# ACC_ICM20948.net
KiCad netlist of a schematic drawn in Altium Designer
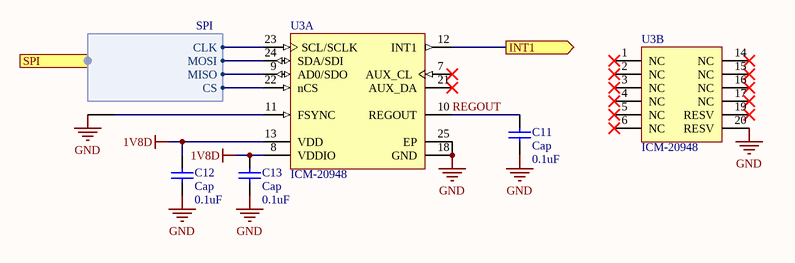
[diagram p0: ACC_ICM20948.SchDoc]

(export (version "E")
  (design (tool "Eeschema 10.0.6"))
  (components
    (comp (ref "C11")
      (value "Cap")
      (footprint "CAPC1005N")
      (description "Capacitor")
      (fields (field (name "ALTIUM_VALUE") "0.1uF") (field (name "PUBLISHER") "Altium Limited"))
      (libsource (lib "Miscellaneous Devices") (part "Cap"))
    )
    (comp (ref "C12")
      (value "Cap")
      (footprint "CAPC1005N")
      (description "Capacitor")
      (fields (field (name "ALTIUM_VALUE") "0.1uF") (field (name "PUBLISHER") "Altium Limited"))
      (libsource (lib "Miscellaneous Devices") (part "Cap"))
    )
    (comp (ref "C13")
      (value "Cap")
      (footprint "CAPC1005N")
      (description "Capacitor")
      (fields (field (name "ALTIUM_VALUE") "0.1uF") (field (name "PUBLISHER") "Altium Limited"))
      (libsource (lib "Miscellaneous Devices") (part "Cap"))
    )
    (comp (ref "U3")
      (value "ICM-20948")
      (footprint "TDK-QFN-24_M")
      (fields (field (name "MANUFACTURER") "TDK"))
      (libsource (lib "Altium Content Vault") (part "TDK-ICM-20948-QFN-24"))
    )
  )
  (nets
    (net (code "2") (name "/CLK") (class "Default")
      (node (ref "U3") (pin "23") (pinfunction "SCL/SCLK_23") (pintype "input"))
    )
    (net (code "3") (name "/CS") (class "Default")
      (node (ref "U3") (pin "22") (pinfunction "nCS_22") (pintype "input"))
    )
    (net (code "4") (name "/INT1") (class "Default")
      (node (ref "U3") (pin "12") (pinfunction "INT1_12") (pintype "output"))
    )
    (net (code "5") (name "/MISO") (class "Default")
      (node (ref "U3") (pin "9") (pinfunction "AD0/SDO_9") (pintype "bidirectional"))
    )
    (net (code "6") (name "/MOSI") (class "Default")
      (node (ref "U3") (pin "24") (pinfunction "SDA/SDI_24") (pintype "bidirectional"))
    )
    (net (code "7") (name "/REGOUT") (class "Default")
      (node (ref "C11") (pin "2") (pinfunction "2_2") (pintype "passive"))
      (node (ref "U3") (pin "10") (pinfunction "REGOUT_10") (pintype "passive"))
    )
    (net (code "9") (name "1V8D") (class "Default")
      (node (ref "C12") (pin "2") (pinfunction "2_2") (pintype "passive"))
      (node (ref "C13") (pin "2") (pinfunction "2_2") (pintype "passive"))
      (node (ref "U3") (pin "13") (pinfunction "VDD_13") (pintype "power_in"))
      (node (ref "U3") (pin "8") (pinfunction "VDDIO_8") (pintype "power_in"))
    )
    (net (code "10") (name "GND") (class "Default")
      (node (ref "C11") (pin "1") (pinfunction "1_1") (pintype "passive"))
      (node (ref "C12") (pin "1") (pinfunction "1_1") (pintype "passive"))
      (node (ref "C13") (pin "1") (pinfunction "1_1") (pintype "passive"))
      (node (ref "U3") (pin "11") (pinfunction "FSYNC_11") (pintype "input"))
      (node (ref "U3") (pin "18") (pinfunction "GND_18") (pintype "power_in"))
      (node (ref "U3") (pin "20") (pinfunction "RESV_20") (pintype "passive"))
      (node (ref "U3") (pin "25") (pinfunction "EP_25") (pintype "passive"))
    )
    (net (code "11") (name "unconnected-(U3A-AUX_CL-Pad7)") (class "Default")
      (node (ref "U3") (pin "7") (pinfunction "AUX_CL_7") (pintype "input+no_connect"))
    )
    (net (code "12") (name "unconnected-(U3A-AUX_DA-Pad21)") (class "Default")
      (node (ref "U3") (pin "21") (pinfunction "AUX_DA_21") (pintype "passive+no_connect"))
    )
    (net (code "13") (name "unconnected-(U3B-NC-Pad1)") (class "Default")
      (node (ref "U3") (pin "1") (pinfunction "NC_1") (pintype "passive+no_connect"))
    )
    (net (code "14") (name "unconnected-(U3B-NC-Pad2)") (class "Default")
      (node (ref "U3") (pin "2") (pinfunction "NC_2") (pintype "passive+no_connect"))
    )
    (net (code "15") (name "unconnected-(U3B-NC-Pad3)") (class "Default")
      (node (ref "U3") (pin "3") (pinfunction "NC_3") (pintype "passive+no_connect"))
    )
    (net (code "16") (name "unconnected-(U3B-NC-Pad4)") (class "Default")
      (node (ref "U3") (pin "4") (pinfunction "NC_4") (pintype "passive+no_connect"))
    )
    (net (code "17") (name "unconnected-(U3B-NC-Pad5)") (class "Default")
      (node (ref "U3") (pin "5") (pinfunction "NC_5") (pintype "passive+no_connect"))
    )
    (net (code "18") (name "unconnected-(U3B-NC-Pad6)") (class "Default")
      (node (ref "U3") (pin "6") (pinfunction "NC_6") (pintype "passive+no_connect"))
    )
    (net (code "19") (name "unconnected-(U3B-NC-Pad14)") (class "Default")
      (node (ref "U3") (pin "14") (pinfunction "NC_14") (pintype "passive+no_connect"))
    )
    (net (code "20") (name "unconnected-(U3B-NC-Pad15)") (class "Default")
      (node (ref "U3") (pin "15") (pinfunction "NC_15") (pintype "passive+no_connect"))
    )
    (net (code "21") (name "unconnected-(U3B-NC-Pad16)") (class "Default")
      (node (ref "U3") (pin "16") (pinfunction "NC_16") (pintype "passive+no_connect"))
    )
    (net (code "22") (name "unconnected-(U3B-NC-Pad17)") (class "Default")
      (node (ref "U3") (pin "17") (pinfunction "NC_17") (pintype "passive+no_connect"))
    )
    (net (code "23") (name "unconnected-(U3B-RESV-Pad19)") (class "Default")
      (node (ref "U3") (pin "19") (pinfunction "RESV_19") (pintype "passive+no_connect"))
    )
  )
)
